# Sheet1.net
KiCad netlist of a schematic drawn in Altium Designer
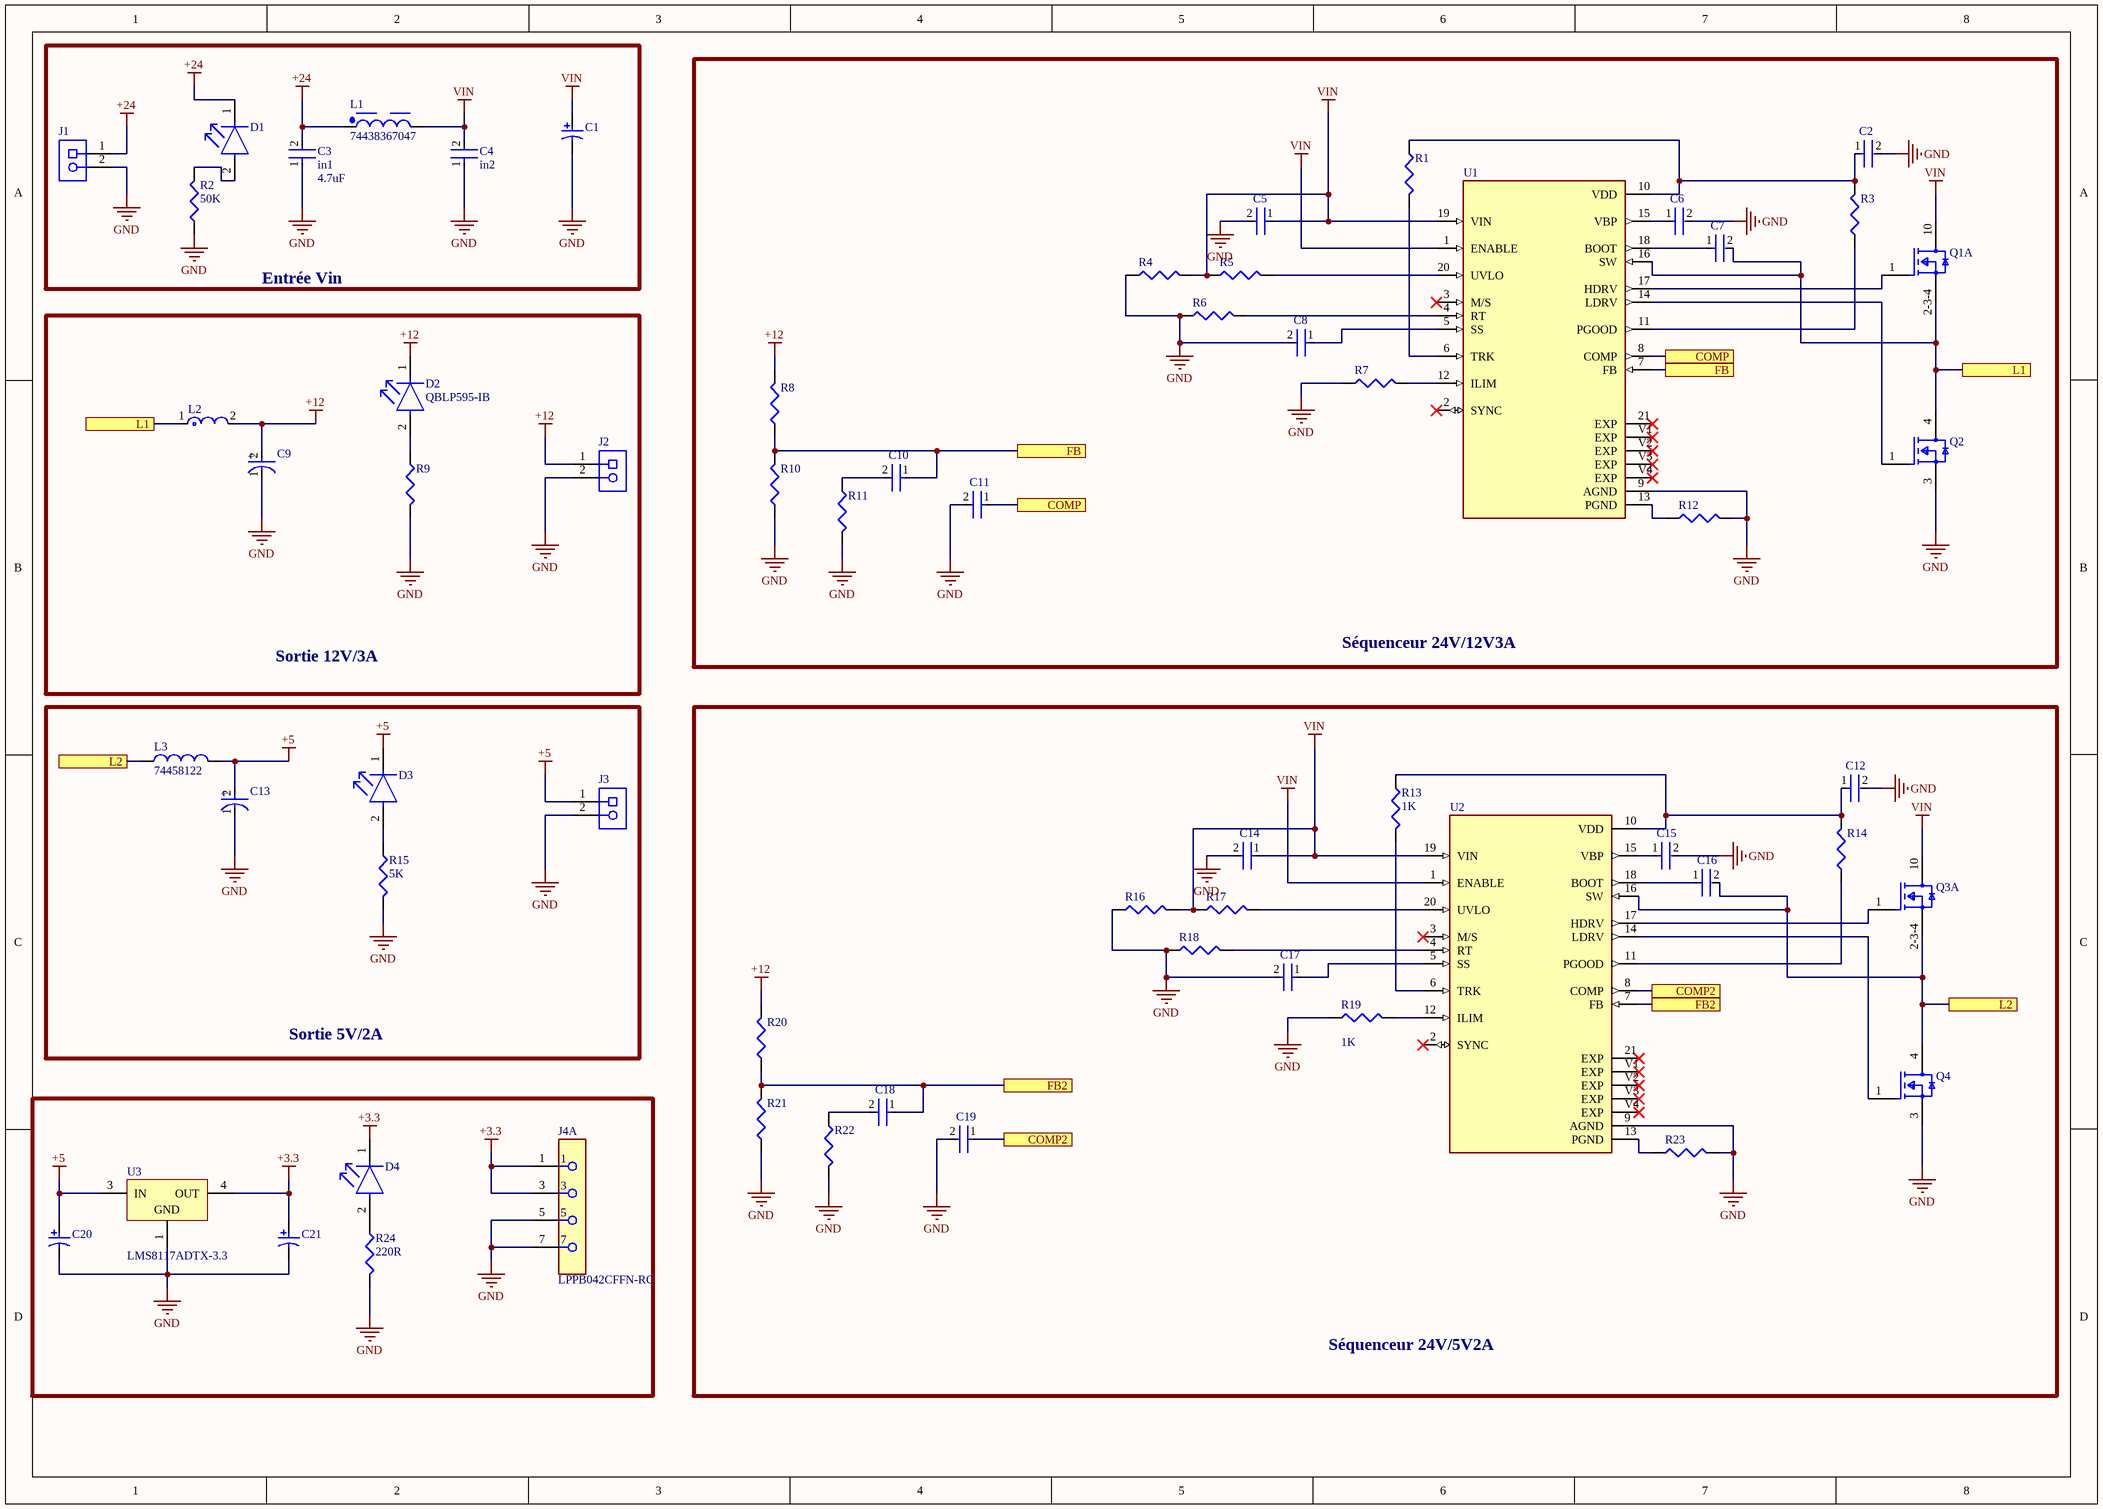
[diagram p0: Sheet1.SchDoc]

(export (version "E")
  (design (tool "Eeschema 10.0.6"))
  (components
    (comp (ref "C1")
      (value "UUD1H100MCL1GS")
      (footprint "NIC-CAPA2-6.3X5.8_V")
      (fields (field (name "MANUFACTURER") "Nichicon"))
      (libsource (lib "Altium Content Vault") (part "NIC-CAP-P-2"))
    )
    (comp (ref "C2")
      (value "~")
      (footprint "FP-0402-L_1_0_0_05-W_0_5-IPC_C")
      (description "None")
      (fields (field (name "TOLERANCE") "10%") (field (name "VOLTAGE") "50V"))
      (libsource (lib "Altium Content Vault") (part "b4654b650e69147ec39a6b967a45e02"))
    )
    (comp (ref "C3")
      (value "in1")
      (footprint "FP-1206-L_3_2_0_2-W_1_6_0-IPC_B")
      (description "None")
      (fields (field (name "TOLERANCE") "10%") (field (name "CAPACITANCE") "4.7uF"))
      (libsource (lib "Altium Content Vault") (part "b4654b650e69147ec39a6b967a45e02"))
    )
    (comp (ref "C4")
      (value "in2")
      (footprint "FP-0402-L_1_0_0_05-W_0_5-IPC_C")
      (description "None")
      (fields (field (name "TOLERANCE") "10%") (field (name "VOLTAGE") "50V"))
      (libsource (lib "Altium Content Vault") (part "b4654b650e69147ec39a6b967a45e02"))
    )
    (comp (ref "C5")
      (value "~")
      (footprint "FP-0402-L_1_0_0_05-W_0_5-IPC_C")
      (description "None")
      (fields (field (name "TOLERANCE") "10%") (field (name "VOLTAGE") "50V"))
      (libsource (lib "Altium Content Vault") (part "b4654b650e69147ec39a6b967a45e02"))
    )
    (comp (ref "C6")
      (value "~")
      (footprint "FP-0402-L_1_0_0_05-W_0_5-IPC_C")
      (description "None")
      (fields (field (name "TOLERANCE") "10%") (field (name "VOLTAGE") "50V"))
      (libsource (lib "Altium Content Vault") (part "b4654b650e69147ec39a6b967a45e02"))
    )
    (comp (ref "C7")
      (value "~")
      (footprint "FP-0402-L_1_0_0_05-W_0_5-IPC_C")
      (description "None")
      (fields (field (name "TOLERANCE") "10%") (field (name "VOLTAGE") "50V"))
      (libsource (lib "Altium Content Vault") (part "b4654b650e69147ec39a6b967a45e02"))
    )
    (comp (ref "C8")
      (value "~")
      (footprint "FP-0402-L_1_0_0_05-W_0_5-IPC_C")
      (description "None")
      (fields (field (name "TOLERANCE") "10%") (field (name "VOLTAGE") "50V"))
      (libsource (lib "Altium Content Vault") (part "b4654b650e69147ec39a6b967a45e02"))
    )
    (comp (ref "C9")
      (value "HHXC500ARA101MJA0G")
      (footprint "FP-HXC-ALA0-MFG")
      (description "CAP ALUM POLY 100UF 20% 50V SMD")
      (fields (field (name "TOLERANCE") "20%"))
      (libsource (lib "Altium Content Vault") (part "203bc49f2ac43e59fd269a8c329ed05"))
    )
    (comp (ref "C10")
      (value "~")
      (footprint "FP-0402-L_1_0_0_05-W_0_5-IPC_C")
      (description "None")
      (fields (field (name "TOLERANCE") "10%") (field (name "VOLTAGE") "50V"))
      (libsource (lib "Altium Content Vault") (part "b4654b650e69147ec39a6b967a45e02"))
    )
    (comp (ref "C11")
      (value "~")
      (footprint "FP-0402-L_1_0_0_05-W_0_5-IPC_C")
      (description "None")
      (fields (field (name "TOLERANCE") "10%") (field (name "VOLTAGE") "50V"))
      (libsource (lib "Altium Content Vault") (part "b4654b650e69147ec39a6b967a45e02"))
    )
    (comp (ref "C12")
      (value "~")
      (footprint "FP-0402-L_1_0_0_05-W_0_5-IPC_C")
      (description "None")
      (fields (field (name "TOLERANCE") "10%") (field (name "VOLTAGE") "50V"))
      (libsource (lib "Altium Content Vault") (part "b4654b650e69147ec39a6b967a45e02"))
    )
    (comp (ref "C13")
      (value "HHXC500ARA101MJA0G")
      (footprint "FP-HXC-ALA0-MFG")
      (description "CAP ALUM POLY 100UF 20% 50V SMD")
      (fields (field (name "TOLERANCE") "20%"))
      (libsource (lib "Altium Content Vault") (part "203bc49f2ac43e59fd269a8c329ed05"))
    )
    (comp (ref "C14")
      (value "~")
      (footprint "FP-0402-L_1_0_0_05-W_0_5-IPC_C")
      (description "None")
      (fields (field (name "TOLERANCE") "10%") (field (name "VOLTAGE") "50V"))
      (libsource (lib "Altium Content Vault") (part "b4654b650e69147ec39a6b967a45e02"))
    )
    (comp (ref "C15")
      (value "~")
      (footprint "FP-0402-L_1_0_0_05-W_0_5-IPC_C")
      (description "None")
      (fields (field (name "TOLERANCE") "10%") (field (name "VOLTAGE") "50V"))
      (libsource (lib "Altium Content Vault") (part "b4654b650e69147ec39a6b967a45e02"))
    )
    (comp (ref "C16")
      (value "~")
      (footprint "FP-0402-L_1_0_0_05-W_0_5-IPC_C")
      (description "None")
      (fields (field (name "TOLERANCE") "10%") (field (name "VOLTAGE") "50V"))
      (libsource (lib "Altium Content Vault") (part "b4654b650e69147ec39a6b967a45e02"))
    )
    (comp (ref "C17")
      (value "~")
      (footprint "FP-0402-L_1_0_0_05-W_0_5-IPC_C")
      (description "None")
      (fields (field (name "TOLERANCE") "10%") (field (name "VOLTAGE") "50V"))
      (libsource (lib "Altium Content Vault") (part "b4654b650e69147ec39a6b967a45e02"))
    )
    (comp (ref "C18")
      (value "~")
      (footprint "FP-0402-L_1_0_0_05-W_0_5-IPC_C")
      (description "None")
      (fields (field (name "TOLERANCE") "10%") (field (name "VOLTAGE") "50V"))
      (libsource (lib "Altium Content Vault") (part "b4654b650e69147ec39a6b967a45e02"))
    )
    (comp (ref "C19")
      (value "~")
      (footprint "FP-0402-L_1_0_0_05-W_0_5-IPC_C")
      (description "None")
      (fields (field (name "TOLERANCE") "10%") (field (name "VOLTAGE") "50V"))
      (libsource (lib "Altium Content Vault") (part "b4654b650e69147ec39a6b967a45e02"))
    )
    (comp (ref "C20")
      (value "UUD1H100MCL1GS")
      (footprint "NIC-CAPA2-6.3X5.8_V")
      (fields (field (name "MANUFACTURER") "Nichicon"))
      (libsource (lib "Altium Content Vault") (part "NIC-CAP-P-2"))
    )
    (comp (ref "C21")
      (value "UUD1H100MCL1GS")
      (footprint "NIC-CAPA2-6.3X5.8_V")
      (fields (field (name "MANUFACTURER") "Nichicon"))
      (libsource (lib "Altium Content Vault") (part "NIC-CAP-P-2"))
    )
    (comp (ref "D1")
      (value "APT1608LZGCK")
      (footprint "FP-APT1608LZGCK-MFG")
      (description "LED GREEN CLEAR 2SMD")
      (libsource (lib "Altium Content Vault") (part "8706943c75ba83719d021d2fdc84c58"))
    )
    (comp (ref "D2")
      (value "QBLP595-IB")
      (footprint "FP-QBLP595-IB-MFG")
      (description "LED BLUE CLEAR 0402 SMD")
      (libsource (lib "Altium Content Vault") (part "8706943c75ba83719d021d2fdc84c58"))
    )
    (comp (ref "D3")
      (value "SML-P11VTT86R")
      (footprint "FP-SML-P1-MFG")
      (description "LED RED CLEAR 1006 SMD")
      (fields
        (field (name "OCTOPART") "https://octopart.com/sml-p11vtt86r-rohm-34112314")
        (field (name "MANUFACTURER") "Rohm")
      )
      (libsource (lib "Altium Content Vault") (part "8706943c75ba83719d021d2fdc84c58"))
    )
    (comp (ref "D4")
      (value "APTD1608SYC/J3")
      (footprint "FP-APTD1608SYC-J3-MFG")
      (description "LED YELLOW CLEAR CHIP SMD")
      (libsource (lib "Altium Content Vault") (part "8706943c75ba83719d021d2fdc84c58"))
    )
    (comp (ref "J1")
      (value "1729128")
      (footprint "PHOE-1729128-2_V")
      (description "PCB Terminal Block, 13.5 A, 400 V, 2-Pin THD, RoHS, Bulk")
      (fields (field (name "MANUFACTURER") "Phoenix Contact"))
      (libsource (lib "Bornier_tension") (part "CMP-2000-05815-1"))
    )
    (comp (ref "J2")
      (value "12V")
      (footprint "PHOE-1729128-2_V")
      (description "PCB Terminal Block, 13.5 A, 400 V, 2-Pin THD, RoHS, Bulk")
      (fields (field (name "PARTNUMBER") "1729128") (field (name "MANUFACTURER") "Phoenix Contact"))
      (libsource (lib "") (part "CMP-2000-05815-1_1"))
    )
    (comp (ref "J3")
      (value "12V")
      (footprint "PHOE-1729128-2_V")
      (description "PCB Terminal Block, 13.5 A, 400 V, 2-Pin THD, RoHS, Bulk")
      (fields (field (name "PARTNUMBER") "1729128") (field (name "MANUFACTURER") "Phoenix Contact"))
      (libsource (lib "") (part "CMP-2000-05815-1_1"))
    )
    (comp (ref "J4")
      (value "LPPB042CFFN-RC")
      (footprint "FP-LPPB042CFFN-RC-MFG")
      (description "CONN HDR 8POS 0.05 GOLD PCB")
      (libsource (lib "Altium Content Vault") (part "f7953d7cc9e5fc6ef8e06ef09a26288"))
    )
    (comp (ref "L1")
      (value "74438367047")
      (footprint "WE-MAPI_5030")
      (description "74438367047 Inductor, 4.7Uh, Shielded, 5.5A Rohs Compliant: Yes")
      (libsource (lib "Altium Content Vault") (part "Inductor - 2"))
    )
    (comp (ref "L2")
      (value "XAL5050-223MEC")
      (footprint "FP-XAL5050-223MEC-MFG")
      (description "Fixed Inductors 22uH Shld 20% 3.4A 99.65mOhms AECQ2")
      (fields (field (name "TOLERANCE") "20%"))
      (libsource (lib "Altium Content Vault") (part "4cc4b267dca4c8e51f7102f422741d8"))
    )
    (comp (ref "L3")
      (value "74458122")
      (footprint "WE-PD4_Type X")
      (fields (field (name "TOLERANCE") "20%"))
      (libsource (lib "Altium Content Vault") (part "Inductor - 1"))
    )
    (comp (ref "Q1")
      (value "HS1")
      (footprint "FP-511DG-MFG")
      (description "FDMC9430L-F085 Dual N-Channel Logic Level PowerTrench® MOSFET 40V, 12A, 8.2mΩ")
      (libsource (lib "Altium Content Vault") (part "0d9e3f628e7b750e6b663d5a6c9e42d"))
    )
    (comp (ref "Q2")
      (value "LS1")
      (footprint "FP-369AS-MFG")
      (description "FDD86581-F085 PowerTrench® MOSFET, N-Channel, 60 V, 25 A, 15 mΩ")
      (libsource (lib "Altium Content Vault") (part "86656c45bbbddc162aead764a772c09"))
    )
    (comp (ref "Q3")
      (value "HS1")
      (footprint "FP-511DG-MFG")
      (description "FDMC9430L-F085 Dual N-Channel Logic Level PowerTrench® MOSFET 40V, 12A, 8.2mΩ")
      (libsource (lib "Altium Content Vault") (part "0d9e3f628e7b750e6b663d5a6c9e42d"))
    )
    (comp (ref "Q4")
      (value "LS1")
      (footprint "FP-369AS-MFG")
      (description "FDD86581-F085 PowerTrench® MOSFET, N-Channel, 60 V, 25 A, 15 mΩ")
      (libsource (lib "Altium Content Vault") (part "86656c45bbbddc162aead764a772c09"))
    )
    (comp (ref "R1")
      (value "Res3")
      (footprint "J1-0603")
      (description "Resistor")
      (fields (field (name "PUBLISHER") "Altium Limited"))
      (libsource (lib "Miscellaneous Devices") (part "Res3"))
    )
    (comp (ref "R2")
      (value "50K")
      (footprint "J1-0603")
      (description "Resistor")
      (fields (field (name "Comment") "Res3") (field (name "PUBLISHER") "Altium Limited"))
      (libsource (lib "Miscellaneous Devices") (part "Res3"))
    )
    (comp (ref "R3")
      (value "Res3")
      (footprint "J1-0603")
      (description "Resistor")
      (fields (field (name "PUBLISHER") "Altium Limited"))
      (libsource (lib "Miscellaneous Devices") (part "Res3"))
    )
    (comp (ref "R4")
      (value "Res3")
      (footprint "J1-0603")
      (description "Resistor")
      (fields (field (name "PUBLISHER") "Altium Limited"))
      (libsource (lib "Miscellaneous Devices") (part "Res3"))
    )
    (comp (ref "R5")
      (value "Res3")
      (footprint "J1-0603")
      (description "Resistor")
      (fields (field (name "PUBLISHER") "Altium Limited"))
      (libsource (lib "Miscellaneous Devices") (part "Res3"))
    )
    (comp (ref "R6")
      (value "Res3")
      (footprint "J1-0603")
      (description "Resistor")
      (fields (field (name "PUBLISHER") "Altium Limited"))
      (libsource (lib "Miscellaneous Devices") (part "Res3"))
    )
    (comp (ref "R7")
      (value "Res3")
      (footprint "J1-0603")
      (description "Resistor")
      (fields (field (name "PUBLISHER") "Altium Limited"))
      (libsource (lib "Miscellaneous Devices") (part "Res3"))
    )
    (comp (ref "R8")
      (value "Res3")
      (footprint "J1-0603")
      (description "Resistor")
      (fields (field (name "PUBLISHER") "Altium Limited"))
      (libsource (lib "Miscellaneous Devices") (part "Res3"))
    )
    (comp (ref "R9")
      (value "Res3")
      (footprint "J1-0603")
      (description "Resistor")
      (fields (field (name "PUBLISHER") "Altium Limited"))
      (libsource (lib "Miscellaneous Devices") (part "Res3"))
    )
    (comp (ref "R10")
      (value "Res3")
      (footprint "J1-0603")
      (description "Resistor")
      (fields (field (name "PUBLISHER") "Altium Limited"))
      (libsource (lib "Miscellaneous Devices") (part "Res3"))
    )
    (comp (ref "R11")
      (value "Res3")
      (footprint "J1-0603")
      (description "Resistor")
      (fields (field (name "PUBLISHER") "Altium Limited"))
      (libsource (lib "Miscellaneous Devices") (part "Res3"))
    )
    (comp (ref "R12")
      (value "Res3")
      (footprint "J1-0603")
      (description "Resistor")
      (fields (field (name "PUBLISHER") "Altium Limited"))
      (libsource (lib "Miscellaneous Devices") (part "Res3"))
    )
    (comp (ref "R13")
      (value "1K")
      (footprint "J1-0603")
      (description "Resistor")
      (fields (field (name "Comment") "Res3") (field (name "PUBLISHER") "Altium Limited"))
      (libsource (lib "Miscellaneous Devices") (part "Res3"))
    )
    (comp (ref "R14")
      (value "Res3")
      (footprint "J1-0603")
      (description "Resistor")
      (fields (field (name "PUBLISHER") "Altium Limited"))
      (libsource (lib "Miscellaneous Devices") (part "Res3"))
    )
    (comp (ref "R15")
      (value "5K")
      (footprint "J1-0603")
      (description "Resistor")
      (fields (field (name "Comment") "Res3") (field (name "PUBLISHER") "Altium Limited"))
      (libsource (lib "Miscellaneous Devices") (part "Res3"))
    )
    (comp (ref "R16")
      (value "Res3")
      (footprint "J1-0603")
      (description "Resistor")
      (fields (field (name "PUBLISHER") "Altium Limited"))
      (libsource (lib "Miscellaneous Devices") (part "Res3"))
    )
    (comp (ref "R17")
      (value "Res3")
      (footprint "J1-0603")
      (description "Resistor")
      (fields (field (name "PUBLISHER") "Altium Limited"))
      (libsource (lib "Miscellaneous Devices") (part "Res3"))
    )
    (comp (ref "R18")
      (value "Res3")
      (footprint "J1-0603")
      (description "Resistor")
      (fields (field (name "PUBLISHER") "Altium Limited"))
      (libsource (lib "Miscellaneous Devices") (part "Res3"))
    )
    (comp (ref "R19")
      (value "1K")
      (footprint "J1-0603")
      (description "Resistor")
      (fields (field (name "Comment") "Res3") (field (name "PUBLISHER") "Altium Limited"))
      (libsource (lib "Miscellaneous Devices") (part "Res3"))
    )
    (comp (ref "R20")
      (value "Res3")
      (footprint "J1-0603")
      (description "Resistor")
      (fields (field (name "PUBLISHER") "Altium Limited"))
      (libsource (lib "Miscellaneous Devices") (part "Res3"))
    )
    (comp (ref "R21")
      (value "Res3")
      (footprint "J1-0603")
      (description "Resistor")
      (fields (field (name "PUBLISHER") "Altium Limited"))
      (libsource (lib "Miscellaneous Devices") (part "Res3"))
    )
    (comp (ref "R22")
      (value "Res3")
      (footprint "J1-0603")
      (description "Resistor")
      (fields (field (name "PUBLISHER") "Altium Limited"))
      (libsource (lib "Miscellaneous Devices") (part "Res3"))
    )
    (comp (ref "R23")
      (value "Res3")
      (footprint "J1-0603")
      (description "Resistor")
      (fields (field (name "PUBLISHER") "Altium Limited"))
      (libsource (lib "Miscellaneous Devices") (part "Res3"))
    )
    (comp (ref "R24")
      (value "220R")
      (footprint "J1-0603")
      (description "Resistor")
      (fields (field (name "Comment") "Res3") (field (name "PUBLISHER") "Altium Limited"))
      (libsource (lib "Miscellaneous Devices") (part "Res3"))
    )
    (comp (ref "U1")
      (value "TPS40170RGYT")
      (footprint "QFN50P350X450X100-21N")
      (description "4.5 V to 60 V Wide-Input Synchronous PWM Buck Controller")
      (fields (field (name "MF") "Texas Instruments"))
      (libsource (lib "TPS40170RGYT") (part "TPS40170RGYT"))
    )
    (comp (ref "U2")
      (value "TPS40170RGYT")
      (footprint "QFN50P350X450X100-21N")
      (description "4.5 V to 60 V Wide-Input Synchronous PWM Buck Controller")
      (fields (field (name "MF") "Texas Instruments"))
      (libsource (lib "TPS40170RGYT") (part "TPS40170RGYT"))
    )
    (comp (ref "U3")
      (value "LMS8117ADTX-3.3")
      (footprint "TD03B_M")
      (description "1A Low-Dropout Linear Regulator, 3-pin TO-252")
      (fields (field (name "MANUFACTURER") "National Semiconductor"))
      (libsource (lib "Altium Content Vault") (part "PM-REG-LMS8117-TO3"))
    )
  )
  (nets
    (net (code "1") (name "+3.3") (class "Default")
      (node (ref "C21") (pin "1") (pinfunction "1_1") (pintype "passive"))
      (node (ref "D4") (pin "1") (pinfunction "C_1") (pintype "passive"))
      (node (ref "J4") (pin "1") (pinfunction "1_1") (pintype "passive"))
      (node (ref "J4") (pin "3") (pinfunction "3_3") (pintype "passive"))
      (node (ref "U3") (pin "4") (pinfunction "OUT_4") (pintype "power_in"))
    )
    (net (code "2") (name "+5") (class "Default")
      (node (ref "C13") (pin "2") (pinfunction "A_2") (pintype "passive"))
      (node (ref "C20") (pin "1") (pinfunction "1_1") (pintype "passive"))
      (node (ref "D3") (pin "1") (pinfunction "C_1") (pintype "passive"))
      (node (ref "J3") (pin "1") (pinfunction "1_1") (pintype "passive"))
      (node (ref "L3") (pin "2") (pinfunction "2_2") (pintype "passive"))
      (node (ref "U3") (pin "3") (pinfunction "IN_3") (pintype "power_in"))
    )
    (net (code "3") (name "+12") (class "Default")
      (node (ref "C9") (pin "2") (pinfunction "A_2") (pintype "passive"))
      (node (ref "D2") (pin "1") (pinfunction "C_1") (pintype "passive"))
      (node (ref "J2") (pin "1") (pinfunction "1_1") (pintype "passive"))
      (node (ref "L2") (pin "2") (pinfunction "2_2") (pintype "passive"))
      (node (ref "R20") (pin "2") (pinfunction "2_2") (pintype "passive"))
      (node (ref "R8") (pin "2") (pinfunction "2_2") (pintype "passive"))
    )
    (net (code "4") (name "+24") (class "Default")
      (node (ref "C3") (pin "2") (pinfunction "2_2") (pintype "passive"))
      (node (ref "D1") (pin "1") (pinfunction "C_1") (pintype "passive"))
      (node (ref "J1") (pin "1") (pinfunction "1_1") (pintype "passive"))
      (node (ref "L1") (pin "1") (pinfunction "1_1") (pintype "passive"))
    )
    (net (code "5") (name "/COMP") (class "Default")
      (node (ref "C11") (pin "1") (pinfunction "1_1") (pintype "passive"))
      (node (ref "U1") (pin "8") (pinfunction "COMP_8") (pintype "output"))
    )
    (net (code "6") (name "/COMP2") (class "Default")
      (node (ref "C19") (pin "1") (pinfunction "1_1") (pintype "passive"))
      (node (ref "U2") (pin "8") (pinfunction "COMP_8") (pintype "output"))
    )
    (net (code "7") (name "/FB") (class "Default")
      (node (ref "C10") (pin "1") (pinfunction "1_1") (pintype "passive"))
      (node (ref "R10") (pin "2") (pinfunction "2_2") (pintype "passive"))
      (node (ref "R8") (pin "1") (pinfunction "1_1") (pintype "passive"))
      (node (ref "U1") (pin "7") (pinfunction "FB_7") (pintype "input"))
    )
    (net (code "8") (name "/FB2") (class "Default")
      (node (ref "C18") (pin "1") (pinfunction "1_1") (pintype "passive"))
      (node (ref "R20") (pin "1") (pinfunction "1_1") (pintype "passive"))
      (node (ref "R21") (pin "2") (pinfunction "2_2") (pintype "passive"))
      (node (ref "U2") (pin "7") (pinfunction "FB_7") (pintype "input"))
    )
    (net (code "9") (name "/L1") (class "Default")
      (node (ref "C7") (pin "2") (pinfunction "2_2") (pintype "passive"))
      (node (ref "L2") (pin "1") (pinfunction "1_1") (pintype "passive"))
      (node (ref "Q1") (pin "2-3-4") (pinfunction "S1_2-3-4") (pintype "passive"))
      (node (ref "Q2") (pin "4") (pinfunction "D_4") (pintype "passive"))
      (node (ref "U1") (pin "16") (pinfunction "SW_16") (pintype "input"))
    )
    (net (code "10") (name "/L2") (class "Default")
      (node (ref "C16") (pin "2") (pinfunction "2_2") (pintype "passive"))
      (node (ref "L3") (pin "1") (pinfunction "1_1") (pintype "passive"))
      (node (ref "Q3") (pin "2-3-4") (pinfunction "S1_2-3-4") (pintype "passive"))
      (node (ref "Q4") (pin "4") (pinfunction "D_4") (pintype "passive"))
      (node (ref "U2") (pin "16") (pinfunction "SW_16") (pintype "input"))
    )
    (net (code "11") (name "GND") (class "Default")
      (node (ref "C1") (pin "2") (pinfunction "2_2") (pintype "passive"))
      (node (ref "C11") (pin "2") (pinfunction "2_2") (pintype "passive"))
      (node (ref "C12") (pin "2") (pinfunction "2_2") (pintype "passive"))
      (node (ref "C13") (pin "1") (pinfunction "C_1") (pintype "passive"))
      (node (ref "C14") (pin "2") (pinfunction "2_2") (pintype "passive"))
      (node (ref "C15") (pin "2") (pinfunction "2_2") (pintype "passive"))
      (node (ref "C17") (pin "2") (pinfunction "2_2") (pintype "passive"))
      (node (ref "C19") (pin "2") (pinfunction "2_2") (pintype "passive"))
      (node (ref "C2") (pin "2") (pinfunction "2_2") (pintype "passive"))
      (node (ref "C20") (pin "2") (pinfunction "2_2") (pintype "passive"))
      (node (ref "C21") (pin "2") (pinfunction "2_2") (pintype "passive"))
      (node (ref "C3") (pin "1") (pinfunction "1_1") (pintype "passive"))
      (node (ref "C4") (pin "1") (pinfunction "1_1") (pintype "passive"))
      (node (ref "C5") (pin "2") (pinfunction "2_2") (pintype "passive"))
      (node (ref "C6") (pin "2") (pinfunction "2_2") (pintype "passive"))
      (node (ref "C8") (pin "2") (pinfunction "2_2") (pintype "passive"))
      (node (ref "C9") (pin "1") (pinfunction "C_1") (pintype "passive"))
      (node (ref "J1") (pin "2") (pinfunction "2_2") (pintype "passive"))
      (node (ref "J2") (pin "2") (pinfunction "2_2") (pintype "passive"))
      (node (ref "J3") (pin "2") (pinfunction "2_2") (pintype "passive"))
      (node (ref "J4") (pin "5") (pinfunction "5_5") (pintype "passive"))
      (node (ref "J4") (pin "7") (pinfunction "7_7") (pintype "passive"))
      (node (ref "Q2") (pin "3") (pinfunction "S_3") (pintype "passive"))
      (node (ref "Q4") (pin "3") (pinfunction "S_3") (pintype "passive"))
      (node (ref "R10") (pin "1") (pinfunction "1_1") (pintype "passive"))
      (node (ref "R11") (pin "2") (pinfunction "2_2") (pintype "passive"))
      (node (ref "R12") (pin "2") (pinfunction "2_2") (pintype "passive"))
      (node (ref "R15") (pin "2") (pinfunction "2_2") (pintype "passive"))
      (node (ref "R16") (pin "1") (pinfunction "1_1") (pintype "passive"))
      (node (ref "R18") (pin "1") (pinfunction "1_1") (pintype "passive"))
      (node (ref "R19") (pin "1") (pinfunction "1_1") (pintype "passive"))
      (node (ref "R2") (pin "1") (pinfunction "1_1") (pintype "passive"))
      (node (ref "R21") (pin "1") (pinfunction "1_1") (pintype "passive"))
      (node (ref "R22") (pin "2") (pinfunction "2_2") (pintype "passive"))
      (node (ref "R23") (pin "2") (pinfunction "2_2") (pintype "passive"))
      (node (ref "R24") (pin "2") (pinfunction "2_2") (pintype "passive"))
      (node (ref "R4") (pin "1") (pinfunction "1_1") (pintype "passive"))
      (node (ref "R6") (pin "1") (pinfunction "1_1") (pintype "passive"))
      (node (ref "R7") (pin "1") (pinfunction "1_1") (pintype "passive"))
      (node (ref "R9") (pin "2") (pinfunction "2_2") (pintype "passive"))
      (node (ref "U1") (pin "9") (pinfunction "AGND_9") (pintype "power_in"))
      (node (ref "U2") (pin "9") (pinfunction "AGND_9") (pintype "power_in"))
      (node (ref "U3") (pin "1") (pinfunction "GND_1") (pintype "power_in"))
    )
    (net (code "12") (name "Net-(C10-Pad2)") (class "Default")
      (node (ref "C10") (pin "2") (pinfunction "2_2") (pintype "passive"))
      (node (ref "R11") (pin "1") (pinfunction "1_1") (pintype "passive"))
    )
    (net (code "13") (name "Net-(C18-Pad2)") (class "Default")
      (node (ref "C18") (pin "2") (pinfunction "2_2") (pintype "passive"))
      (node (ref "R22") (pin "1") (pinfunction "1_1") (pintype "passive"))
    )
    (net (code "14") (name "Net-(D1-A)") (class "Default")
      (node (ref "D1") (pin "2") (pinfunction "A_2") (pintype "passive"))
      (node (ref "R2") (pin "2") (pinfunction "2_2") (pintype "passive"))
    )
    (net (code "15") (name "Net-(D2-A)") (class "Default")
      (node (ref "D2") (pin "2") (pinfunction "A_2") (pintype "passive"))
      (node (ref "R9") (pin "1") (pinfunction "1_1") (pintype "passive"))
    )
    (net (code "16") (name "Net-(D3-A)") (class "Default")
      (node (ref "D3") (pin "2") (pinfunction "A_2") (pintype "passive"))
      (node (ref "R15") (pin "1") (pinfunction "1_1") (pintype "passive"))
    )
    (net (code "17") (name "Net-(D4-A)") (class "Default")
      (node (ref "D4") (pin "2") (pinfunction "A_2") (pintype "passive"))
      (node (ref "R24") (pin "1") (pinfunction "1_1") (pintype "passive"))
    )
    (net (code "18") (name "Net-(Q1A-G1)") (class "Default")
      (node (ref "Q1") (pin "1") (pinfunction "G1_1") (pintype "passive"))
      (node (ref "U1") (pin "17") (pinfunction "HDRV_17") (pintype "output"))
    )
    (net (code "19") (name "Net-(Q2-G)") (class "Default")
      (node (ref "Q2") (pin "1") (pinfunction "G_1") (pintype "passive"))
      (node (ref "U1") (pin "14") (pinfunction "LDRV_14") (pintype "output"))
    )
    (net (code "20") (name "Net-(Q3A-G1)") (class "Default")
      (node (ref "Q3") (pin "1") (pinfunction "G1_1") (pintype "passive"))
      (node (ref "U2") (pin "17") (pinfunction "HDRV_17") (pintype "output"))
    )
    (net (code "21") (name "Net-(Q4-G)") (class "Default")
      (node (ref "Q4") (pin "1") (pinfunction "G_1") (pintype "passive"))
      (node (ref "U2") (pin "14") (pinfunction "LDRV_14") (pintype "output"))
    )
    (net (code "22") (name "Net-(U1-BOOT)") (class "Default")
      (node (ref "C7") (pin "1") (pinfunction "1_1") (pintype "passive"))
      (node (ref "U1") (pin "18") (pinfunction "BOOT_18") (pintype "output"))
    )
    (net (code "23") (name "Net-(U1-ILIM)") (class "Default")
      (node (ref "R7") (pin "2") (pinfunction "2_2") (pintype "passive"))
      (node (ref "U1") (pin "12") (pinfunction "ILIM_12") (pintype "input"))
    )
    (net (code "24") (name "Net-(U1-PGND)") (class "Default")
      (node (ref "R12") (pin "1") (pinfunction "1_1") (pintype "passive"))
      (node (ref "U1") (pin "13") (pinfunction "PGND_13") (pintype "power_in"))
    )
    (net (code "25") (name "Net-(U1-PGOOD)") (class "Default")
      (node (ref "R3") (pin "1") (pinfunction "1_1") (pintype "passive"))
      (node (ref "U1") (pin "11") (pinfunction "PGOOD_11") (pintype "output"))
    )
    (net (code "26") (name "Net-(U1-RT)") (class "Default")
      (node (ref "R6") (pin "2") (pinfunction "2_2") (pintype "passive"))
      (node (ref "U1") (pin "4") (pinfunction "RT_4") (pintype "input"))
    )
    (net (code "27") (name "Net-(U1-SS)") (class "Default")
      (node (ref "C8") (pin "1") (pinfunction "1_1") (pintype "passive"))
      (node (ref "U1") (pin "5") (pinfunction "SS_5") (pintype "input"))
    )
    (net (code "28") (name "Net-(U1-TRK)") (class "Default")
      (node (ref "R1") (pin "2") (pinfunction "2_2") (pintype "passive"))
      (node (ref "U1") (pin "6") (pinfunction "TRK_6") (pintype "input"))
    )
    (net (code "29") (name "Net-(U1-UVLO)") (class "Default")
      (node (ref "R5") (pin "2") (pinfunction "2_2") (pintype "passive"))
      (node (ref "U1") (pin "20") (pinfunction "UVLO_20") (pintype "input"))
    )
    (net (code "30") (name "Net-(U1-VBP)") (class "Default")
      (node (ref "C6") (pin "1") (pinfunction "1_1") (pintype "passive"))
      (node (ref "U1") (pin "15") (pinfunction "VBP_15") (pintype "output"))
    )
    (net (code "31") (name "Net-(U1-VDD)") (class "Default")
      (node (ref "C2") (pin "1") (pinfunction "1_1") (pintype "passive"))
      (node (ref "R1") (pin "1") (pinfunction "1_1") (pintype "passive"))
      (node (ref "R3") (pin "2") (pinfunction "2_2") (pintype "passive"))
      (node (ref "U1") (pin "10") (pinfunction "VDD_10") (pintype "power_in"))
    )
    (net (code "32") (name "Net-(U2-BOOT)") (class "Default")
      (node (ref "C16") (pin "1") (pinfunction "1_1") (pintype "passive"))
      (node (ref "U2") (pin "18") (pinfunction "BOOT_18") (pintype "output"))
    )
    (net (code "33") (name "Net-(U2-ILIM)") (class "Default")
      (node (ref "R19") (pin "2") (pinfunction "2_2") (pintype "passive"))
      (node (ref "U2") (pin "12") (pinfunction "ILIM_12") (pintype "input"))
    )
    (net (code "34") (name "Net-(U2-PGND)") (class "Default")
      (node (ref "R23") (pin "1") (pinfunction "1_1") (pintype "passive"))
      (node (ref "U2") (pin "13") (pinfunction "PGND_13") (pintype "power_in"))
    )
    (net (code "35") (name "Net-(U2-PGOOD)") (class "Default")
      (node (ref "R14") (pin "1") (pinfunction "1_1") (pintype "passive"))
      (node (ref "U2") (pin "11") (pinfunction "PGOOD_11") (pintype "output"))
    )
    (net (code "36") (name "Net-(U2-RT)") (class "Default")
      (node (ref "R18") (pin "2") (pinfunction "2_2") (pintype "passive"))
      (node (ref "U2") (pin "4") (pinfunction "RT_4") (pintype "input"))
    )
    (net (code "37") (name "Net-(U2-SS)") (class "Default")
      (node (ref "C17") (pin "1") (pinfunction "1_1") (pintype "passive"))
      (node (ref "U2") (pin "5") (pinfunction "SS_5") (pintype "input"))
    )
    (net (code "38") (name "Net-(U2-TRK)") (class "Default")
      (node (ref "R13") (pin "2") (pinfunction "2_2") (pintype "passive"))
      (node (ref "U2") (pin "6") (pinfunction "TRK_6") (pintype "input"))
    )
    (net (code "39") (name "Net-(U2-UVLO)") (class "Default")
      (node (ref "R17") (pin "2") (pinfunction "2_2") (pintype "passive"))
      (node (ref "U2") (pin "20") (pinfunction "UVLO_20") (pintype "input"))
    )
    (net (code "40") (name "Net-(U2-VBP)") (class "Default")
      (node (ref "C15") (pin "1") (pinfunction "1_1") (pintype "passive"))
      (node (ref "U2") (pin "15") (pinfunction "VBP_15") (pintype "output"))
    )
    (net (code "41") (name "Net-(U2-VDD)") (class "Default")
      (node (ref "C12") (pin "1") (pinfunction "1_1") (pintype "passive"))
      (node (ref "R13") (pin "1") (pinfunction "1_1") (pintype "passive"))
      (node (ref "R14") (pin "2") (pinfunction "2_2") (pintype "passive"))
      (node (ref "U2") (pin "10") (pinfunction "VDD_10") (pintype "power_in"))
    )
    (net (code "42") (name "VIN") (class "Default")
      (node (ref "C1") (pin "1") (pinfunction "1_1") (pintype "passive"))
      (node (ref "C14") (pin "1") (pinfunction "1_1") (pintype "passive"))
      (node (ref "C4") (pin "2") (pinfunction "2_2") (pintype "passive"))
      (node (ref "C5") (pin "1") (pinfunction "1_1") (pintype "passive"))
      (node (ref "L1") (pin "2") (pinfunction "2_2") (pintype "passive"))
      (node (ref "Q1") (pin "10") (pinfunction "D1_10") (pintype "passive"))
      (node (ref "Q3") (pin "10") (pinfunction "D1_10") (pintype "passive"))
      (node (ref "R16") (pin "2") (pinfunction "2_2") (pintype "passive"))
      (node (ref "R17") (pin "1") (pinfunction "1_1") (pintype "passive"))
      (node (ref "R4") (pin "2") (pinfunction "2_2") (pintype "passive"))
      (node (ref "R5") (pin "1") (pinfunction "1_1") (pintype "passive"))
      (node (ref "U1") (pin "1") (pinfunction "ENABLE_1") (pintype "input"))
      (node (ref "U1") (pin "19") (pinfunction "VIN_19") (pintype "input"))
      (node (ref "U2") (pin "1") (pinfunction "ENABLE_1") (pintype "input"))
      (node (ref "U2") (pin "19") (pinfunction "VIN_19") (pintype "input"))
    )
    (net (code "43") (name "unconnected-(U1-EXP-Pad21)") (class "Default")
      (node (ref "U1") (pin "21") (pinfunction "EXP_21") (pintype "passive+no_connect"))
    )
    (net (code "44") (name "unconnected-(U1-EXP-PadV1)") (class "Default")
      (node (ref "U1") (pin "V1") (pinfunction "EXP_V1") (pintype "passive+no_connect"))
    )
    (net (code "45") (name "unconnected-(U1-EXP-PadV2)") (class "Default")
      (node (ref "U1") (pin "V2") (pinfunction "EXP_V2") (pintype "passive+no_connect"))
    )
    (net (code "46") (name "unconnected-(U1-EXP-PadV3)") (class "Default")
      (node (ref "U1") (pin "V3") (pinfunction "EXP_V3") (pintype "passive+no_connect"))
    )
    (net (code "47") (name "unconnected-(U1-EXP-PadV4)") (class "Default")
      (node (ref "U1") (pin "V4") (pinfunction "EXP_V4") (pintype "passive+no_connect"))
    )
    (net (code "48") (name "unconnected-(U1-M{slash}S-Pad3)") (class "Default")
      (node (ref "U1") (pin "3") (pinfunction "M/S_3") (pintype "input+no_connect"))
    )
    (net (code "49") (name "unconnected-(U1-SYNC-Pad2)") (class "Default")
      (node (ref "U1") (pin "2") (pinfunction "SYNC_2") (pintype "bidirectional+no_connect"))
    )
    (net (code "50") (name "unconnected-(U2-EXP-Pad21)") (class "Default")
      (node (ref "U2") (pin "21") (pinfunction "EXP_21") (pintype "passive+no_connect"))
    )
    (net (code "51") (name "unconnected-(U2-EXP-PadV1)") (class "Default")
      (node (ref "U2") (pin "V1") (pinfunction "EXP_V1") (pintype "passive+no_connect"))
    )
    (net (code "52") (name "unconnected-(U2-EXP-PadV2)") (class "Default")
      (node (ref "U2") (pin "V2") (pinfunction "EXP_V2") (pintype "passive+no_connect"))
    )
    (net (code "53") (name "unconnected-(U2-EXP-PadV3)") (class "Default")
      (node (ref "U2") (pin "V3") (pinfunction "EXP_V3") (pintype "passive+no_connect"))
    )
    (net (code "54") (name "unconnected-(U2-EXP-PadV4)") (class "Default")
      (node (ref "U2") (pin "V4") (pinfunction "EXP_V4") (pintype "passive+no_connect"))
    )
    (net (code "55") (name "unconnected-(U2-M{slash}S-Pad3)") (class "Default")
      (node (ref "U2") (pin "3") (pinfunction "M/S_3") (pintype "input+no_connect"))
    )
    (net (code "56") (name "unconnected-(U2-SYNC-Pad2)") (class "Default")
      (node (ref "U2") (pin "2") (pinfunction "SYNC_2") (pintype "bidirectional+no_connect"))
    )
  )
)
